# Relay_Driver.net
KiCad netlist of a schematic drawn in Altium Designer
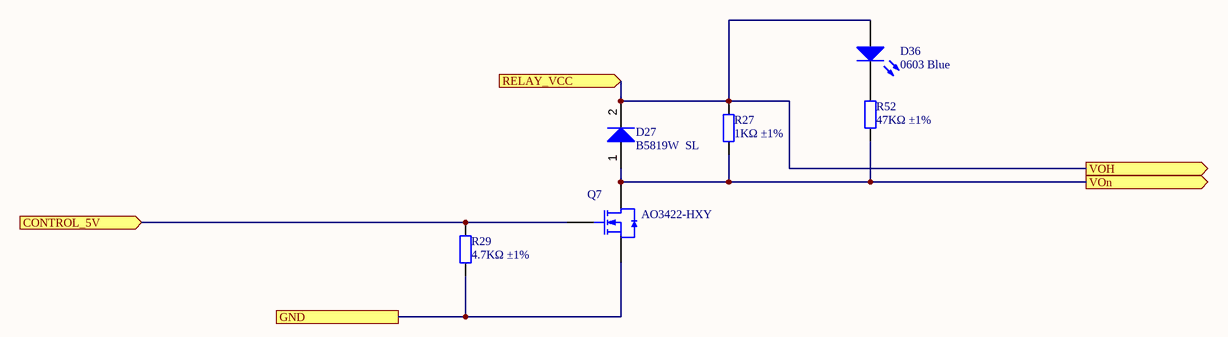
[diagram p0: Relay_Driver.SchDoc]

(export (version "E")
  (design (tool "Eeschema 10.0.6"))
  (components
    (comp (ref "D27")
      (value "B5819W  SL")
      (footprint "SOD-123")
      (description "Schottky Diode")
      (libsource (lib "Diode") (part "SOD-123 B5819W  SL"))
    )
    (comp (ref "D36")
      (value "0603 Blue")
      (footprint "0603_LED_S1")
      (description "LED")
      (libsource (lib "LED") (part "0603 LED Blue"))
    )
    (comp (ref "Q7")
      (value "AO3422-HXY")
      (footprint "SOT-23-3L")
      (description "60V 4.5A 8W 75mΩ@10V,5A 2.5V@250uA N Channel 695pF@15V SOT-23-3L MOSFETs ROHS")
      (libsource (lib "MOS") (part "AO3400A N道沟 X0YV1T SOT-23"))
    )
    (comp (ref "R27")
      (value "1KΩ ±1%")
      (footprint "0603_R")
      (description "Chip resistor")
      (fields (field (name "MANUFACTURER") "Uniroyal Elec") (field (name "PARTNUMBER") "0603WAF1001T5E"))
      (libsource (lib "RES") (part "0603 1K (1001) 1%"))
    )
    (comp (ref "R29")
      (value "4.7KΩ ±1%")
      (footprint "0603_R")
      (description "Chip resistor")
      (fields (field (name "MANUFACTURER") "Uniroyal Elec") (field (name "PARTNUMBER") "0603WAF4701T5E"))
      (libsource (lib "RES") (part "0603 4.7K (4701) 1%"))
    )
    (comp (ref "R52")
      (value "47KΩ ±1%")
      (footprint "0603_R")
      (description "Chip resistor")
      (fields (field (name "MANUFACTURER") "Uniroyal Elec") (field (name "PARTNUMBER") "0603WAF4702T5E"))
      (libsource (lib "RES") (part "0603 47K (4702) 1%"))
    )
  )
  (nets
    (net (code "1") (name "/CONTROL_5V") (class "Default")
      (node (ref "Q7") (pin "1") (pinfunction "G_1") (pintype "passive"))
      (node (ref "R29") (pin "2") (pinfunction "2_2") (pintype "passive"))
    )
    (net (code "2") (name "/GND") (class "Default")
      (node (ref "Q7") (pin "2") (pinfunction "S_2") (pintype "passive"))
      (node (ref "R29") (pin "1") (pinfunction "1_1") (pintype "passive"))
    )
    (net (code "3") (name "/RELAY_VCC") (class "Default")
      (node (ref "D27") (pin "2") (pinfunction "K_2") (pintype "passive"))
      (node (ref "D36") (pin "A") (pinfunction "A_A") (pintype "passive"))
      (node (ref "R27") (pin "2") (pinfunction "2_2") (pintype "passive"))
    )
    (net (code "4") (name "/VOn") (class "Default")
      (node (ref "D27") (pin "1") (pinfunction "A_1") (pintype "passive"))
      (node (ref "Q7") (pin "3") (pinfunction "D_3") (pintype "passive"))
      (node (ref "R27") (pin "1") (pinfunction "1_1") (pintype "passive"))
      (node (ref "R52") (pin "1") (pinfunction "1_1") (pintype "passive"))
    )
    (net (code "5") (name "Net-(D36-PadK)") (class "Default")
      (node (ref "D36") (pin "K") (pinfunction "K_K") (pintype "passive"))
      (node (ref "R52") (pin "2") (pinfunction "2_2") (pintype "passive"))
    )
  )
)
